# YiWallet-Enc-memory.net
KiCad netlist of a schematic drawn in Altium Designer
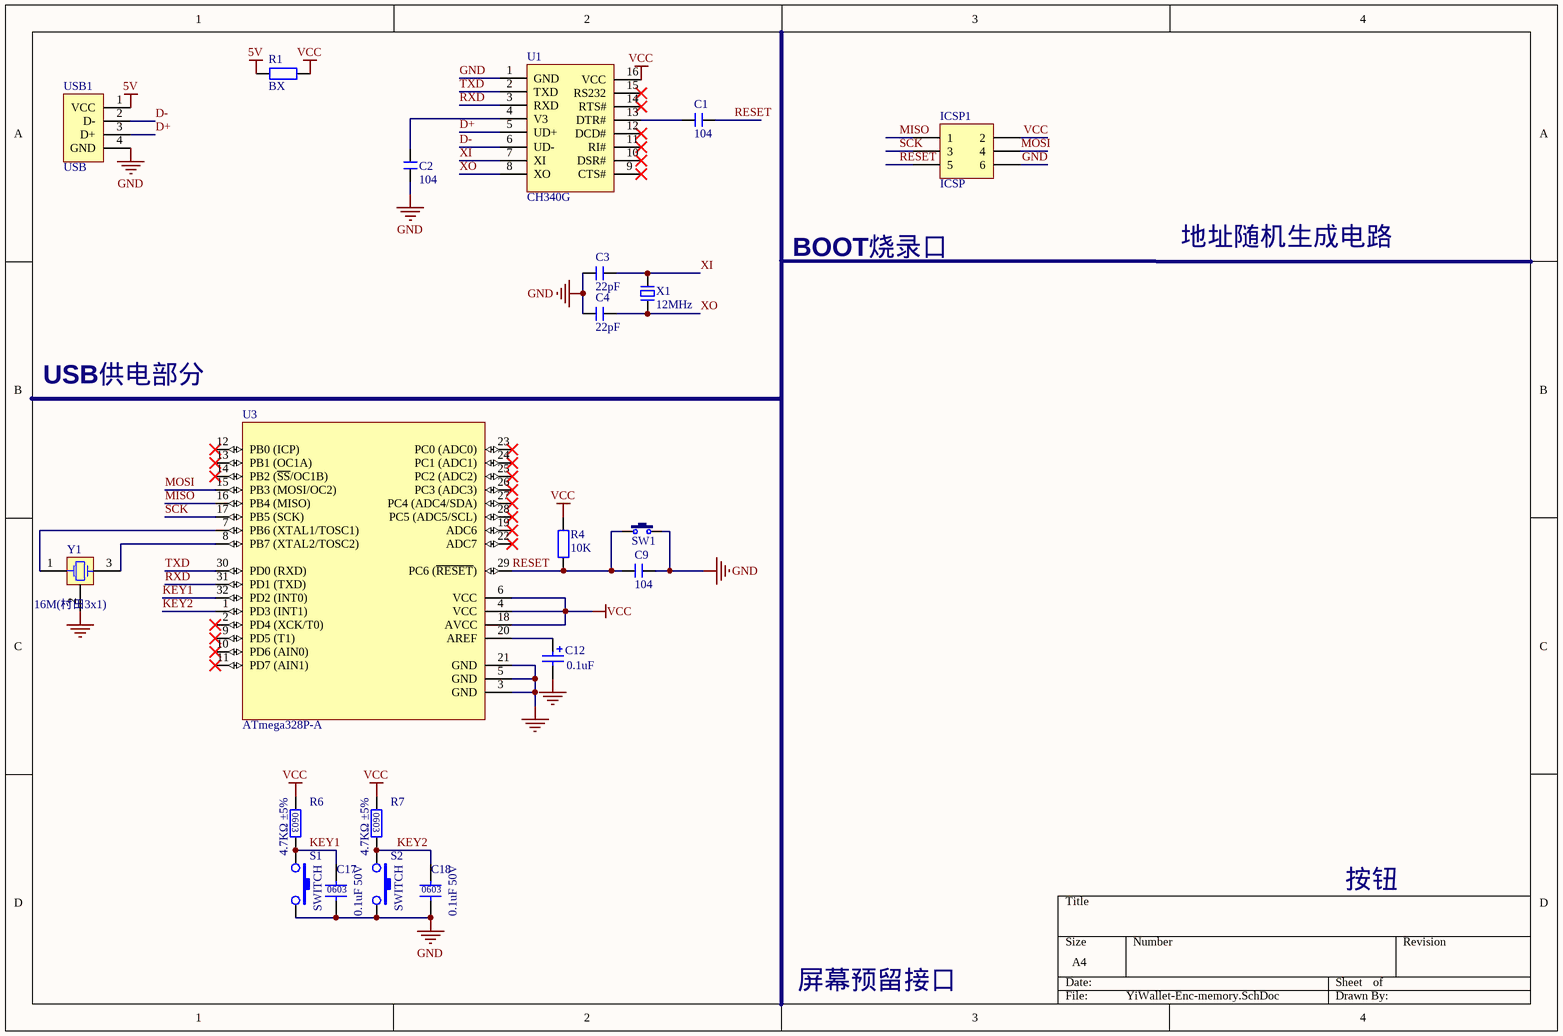
[diagram p0: YiWallet-Enc-memory.SchDoc]

(export (version "E")
  (design (tool "Eeschema 10.0.6"))
  (components
    (comp (ref "C1")
      (value "104")
      (footprint "C 0603_L")
      (description "无极性贴片电容")
      (fields (field (name "版权归属") "源创客"))
      (libsource (lib "3.1   - 电阻-电容-电感") (part "C"))
    )
    (comp (ref "C2")
      (value "104")
      (footprint "C 0603_L")
      (description "无极性贴片电容")
      (fields (field (name "版权归属") "源创客"))
      (libsource (lib "3.1   - 电阻-电容-电感") (part "C"))
    )
    (comp (ref "C3")
      (value "22pF")
      (footprint "C 0603_L")
      (description "无极性贴片电容")
      (fields (field (name "版权归属") "源创客"))
      (libsource (lib "3.1   - 电阻-电容-电感") (part "C"))
    )
    (comp (ref "C4")
      (value "22pF")
      (footprint "C 0603_L")
      (description "无极性贴片电容")
      (fields (field (name "版权归属") "源创客"))
      (libsource (lib "3.1   - 电阻-电容-电感") (part "C"))
    )
    (comp (ref "C9")
      (value "104")
      (footprint "C 0603_L")
      (description "无极性贴片电容")
      (fields (field (name "版权归属") "源创客"))
      (libsource (lib "3.1   - 电阻-电容-电感") (part "C"))
    )
    (comp (ref "C12")
      (value "0.1uF")
      (footprint "C 0603_L")
      (description "Polarized Capacitor (Surface Mount)")
      (fields (field (name "PUBLISHER") "Altium Limited"))
      (libsource (lib "Miscellaneous Devices") (part "Cap Pol3"))
    )
    (comp (ref "C17")
      (value "0.1uF 50V")
      (footprint "C 0603_L")
      (description "贴片电容 0.1uF 50V ±10% -55~+125℃ 0603 X7R CL10B104KB8NNNC")
      (libsource (lib "CLOU-BZ-BetaV0") (part "C-0.1uF 50V 0603"))
    )
    (comp (ref "C18")
      (value "0.1uF 50V")
      (footprint "C 0603_L")
      (description "贴片电容 0.1uF 50V ±10% -55~+125℃ 0603 X7R CL10B104KB8NNNC")
      (libsource (lib "CLOU-BZ-BetaV0") (part "C-0.1uF 50V 0603"))
    )
    (comp (ref "ICSP1")
      (value "ICSP")
      (footprint "HDR2X3")
      (description "Header, 3-Pin, Dual row")
      (fields (field (name "PUBLISHER") "Altium Limited"))
      (libsource (lib "Miscellaneous Connectors") (part "Header 3X2"))
    )
    (comp (ref "R1")
      (value "BX")
      (footprint "R 0603_L")
      (description "贴片电阻")
      (fields (field (name "版权归属") "源创客"))
      (libsource (lib "3.1   - 电阻-电容-电感") (part "R"))
    )
    (comp (ref "R4")
      (value "10K")
      (footprint "R 0603_L")
      (description "贴片电阻")
      (fields (field (name "版权归属") "源创客"))
      (libsource (lib "3.1   - 电阻-电容-电感") (part "R"))
    )
    (comp (ref "R6")
      (value "4.7KΩ ±5%")
      (footprint "C 0603_L")
      (description "贴片电阻 4.7KΩ 1/10W ±5% ±200ppm 0603")
      (libsource (lib "CLOU-BZ-BetaV0") (part "R-4K7 0603 5%"))
    )
    (comp (ref "R7")
      (value "4.7KΩ ±5%")
      (footprint "C 0603_L")
      (description "贴片电阻 4.7KΩ 1/10W ±5% ±200ppm 0603")
      (libsource (lib "CLOU-BZ-BetaV0") (part "R-4K7 0603 5%"))
    )
    (comp (ref "S1")
      (value "SWITCH")
      (footprint "TSW 3*6*4.3-S-W")
      (description "开关（轻触）")
      (libsource (lib "NEW library") (part "SW_PB6.2*6.2_5"))
    )
    (comp (ref "S2")
      (value "SWITCH")
      (footprint "TSW 3*6*4.3-S-W")
      (description "开关（轻触）")
      (libsource (lib "NEW library") (part "SW_PB6.2*6.2_5"))
    )
    (comp (ref "SW1")
      (value "3x6x5")
      (footprint "TSW 3*6*4.3-S-W")
      (description "3x6轻触开关")
      (fields (field (name "版权归属") "源创客"))
      (libsource (lib "5.1   - 按键-开关") (part "TSW 3x6"))
    )
    (comp (ref "U1") (value "CH340G") (footprint "SO-16") (libsource (lib "PCB_Project") (part "CH340G")))
    (comp (ref "U3")
      (value "ATmega328P-A")
      (footprint "TQFP32-7*7")
      (description "8-Bit AVR Microcontroller with 8K Bytes of In-System Programmable Flash Memory")
      (libsource (lib "Atmel Microcontroller 8-Bit AVR") (part "ATmega8-16AC"))
    )
    (comp (ref "USB1")
      (value "USB")
      (footprint "USB_A/P_A")
      (description "USB-A型公接口")
      (fields (field (name "版权归属") "源创客"))
      (libsource (lib "4.1   - 接口类") (part "USB-A/P"))
    )
    (comp (ref "X1")
      (value "12MHz")
      (footprint "OSC HC-49S")
      (description "2脚无源脚晶振")
      (fields (field (name "版权归属") "源创客"))
      (libsource (lib "10.1 - 保险丝-晶振") (part "XTAL-2P"))
    )
    (comp (ref "Y1")
      (value "16M(村田3x1)")
      (footprint "X-CPX20")
      (description "Crystal Oscillator, 3rd In-Line Lead Version")
      (fields (field (name "PUBLISHER") "Altium Limited"))
      (libsource (lib "ECS Crystal Oscillator") (part "ECS-35-17-4-3IL"))
    )
  )
  (nets
    (net (code "1") (name "/D+") (class "Default")
      (node (ref "U1") (pin "5") (pinfunction "UD+_5") (pintype "passive"))
      (node (ref "USB1") (pin "3") (pinfunction "D+_3") (pintype "passive"))
    )
    (net (code "2") (name "/D-") (class "Default")
      (node (ref "U1") (pin "6") (pinfunction "UD-_6") (pintype "passive"))
      (node (ref "USB1") (pin "2") (pinfunction "D-_2") (pintype "passive"))
    )
    (net (code "3") (name "/KEY1") (class "Default")
      (node (ref "C17") (pin "1") (pinfunction "1_1") (pintype "passive"))
      (node (ref "R6") (pin "2") (pinfunction "2_2") (pintype "passive"))
      (node (ref "S1") (pin "2") (pinfunction "2_2") (pintype "passive"))
      (node (ref "U3") (pin "32") (pinfunction "PD2_(INT0)_32") (pintype "bidirectional"))
    )
    (net (code "4") (name "/KEY2") (class "Default")
      (node (ref "C18") (pin "1") (pinfunction "1_1") (pintype "passive"))
      (node (ref "R7") (pin "2") (pinfunction "2_2") (pintype "passive"))
      (node (ref "S2") (pin "2") (pinfunction "2_2") (pintype "passive"))
      (node (ref "U3") (pin "1") (pinfunction "PD3_(INT1)_1") (pintype "bidirectional"))
    )
    (net (code "5") (name "/MISO") (class "Default")
      (node (ref "ICSP1") (pin "1") (pinfunction "1_1") (pintype "passive"))
      (node (ref "U3") (pin "16") (pinfunction "PB4_(MISO)_16") (pintype "bidirectional"))
    )
    (net (code "6") (name "/MOSI") (class "Default")
      (node (ref "ICSP1") (pin "4") (pinfunction "4_4") (pintype "passive"))
      (node (ref "U3") (pin "15") (pinfunction "PB3_(MOSI/OC2)_15") (pintype "bidirectional"))
    )
    (net (code "7") (name "/RESET") (class "Default")
      (node (ref "C1") (pin "2") (pinfunction "2_2") (pintype "passive"))
      (node (ref "C9") (pin "1") (pinfunction "1_1") (pintype "passive"))
      (node (ref "ICSP1") (pin "5") (pinfunction "5_5") (pintype "passive"))
      (node (ref "R4") (pin "1") (pinfunction "1_1") (pintype "passive"))
      (node (ref "SW1") (pin "1") (pinfunction "1_1") (pintype "passive"))
      (node (ref "U3") (pin "29") (pinfunction "PC6_(~{RESET})_29") (pintype "bidirectional"))
    )
    (net (code "8") (name "/RXD") (class "Default")
      (node (ref "U1") (pin "3") (pinfunction "RXD_3") (pintype "passive"))
      (node (ref "U3") (pin "31") (pinfunction "PD1_(TXD)_31") (pintype "bidirectional"))
    )
    (net (code "9") (name "/SCK") (class "Default")
      (node (ref "ICSP1") (pin "3") (pinfunction "3_3") (pintype "passive"))
      (node (ref "U3") (pin "17") (pinfunction "PB5_(SCK)_17") (pintype "bidirectional"))
    )
    (net (code "10") (name "/TXD") (class "Default")
      (node (ref "U1") (pin "2") (pinfunction "TXD_2") (pintype "passive"))
      (node (ref "U3") (pin "30") (pinfunction "PD0_(RXD)_30") (pintype "bidirectional"))
    )
    (net (code "11") (name "/XI") (class "Default")
      (node (ref "C3") (pin "2") (pinfunction "2_2") (pintype "passive"))
      (node (ref "U1") (pin "7") (pinfunction "XI_7") (pintype "passive"))
      (node (ref "X1") (pin "2") (pinfunction "2_2") (pintype "passive"))
    )
    (net (code "12") (name "/XO") (class "Default")
      (node (ref "C4") (pin "2") (pinfunction "2_2") (pintype "passive"))
      (node (ref "U1") (pin "8") (pinfunction "XO_8") (pintype "passive"))
      (node (ref "X1") (pin "1") (pinfunction "1_1") (pintype "passive"))
    )
    (net (code "13") (name "5V") (class "Default")
      (node (ref "R1") (pin "1") (pinfunction "1_1") (pintype "passive"))
      (node (ref "USB1") (pin "1") (pinfunction "VCC_1") (pintype "passive"))
    )
    (net (code "14") (name "GND") (class "Default")
      (node (ref "C12") (pin "2") (pinfunction "2_2") (pintype "passive"))
      (node (ref "C17") (pin "2") (pinfunction "2_2") (pintype "passive"))
      (node (ref "C18") (pin "2") (pinfunction "2_2") (pintype "passive"))
      (node (ref "C2") (pin "1") (pinfunction "1_1") (pintype "passive"))
      (node (ref "C3") (pin "1") (pinfunction "1_1") (pintype "passive"))
      (node (ref "C4") (pin "1") (pinfunction "1_1") (pintype "passive"))
      (node (ref "C9") (pin "2") (pinfunction "2_2") (pintype "passive"))
      (node (ref "ICSP1") (pin "6") (pinfunction "6_6") (pintype "passive"))
      (node (ref "S1") (pin "1") (pinfunction "1_1") (pintype "passive"))
      (node (ref "S2") (pin "1") (pinfunction "1_1") (pintype "passive"))
      (node (ref "SW1") (pin "2") (pinfunction "2_2") (pintype "passive"))
      (node (ref "U1") (pin "1") (pinfunction "GND_1") (pintype "passive"))
      (node (ref "U3") (pin "21") (pinfunction "GND_21") (pintype "power_in"))
      (node (ref "U3") (pin "3") (pinfunction "GND_3") (pintype "power_in"))
      (node (ref "U3") (pin "5") (pinfunction "GND_5") (pintype "power_in"))
      (node (ref "USB1") (pin "4") (pinfunction "GND_4") (pintype "passive"))
      (node (ref "Y1") (pin "2") (pinfunction "COM_2") (pintype "passive"))
    )
    (net (code "15") (name "Net-(U1-DTR#)") (class "Default")
      (node (ref "C1") (pin "1") (pinfunction "1_1") (pintype "passive"))
      (node (ref "U1") (pin "13") (pinfunction "DTR#_13") (pintype "passive"))
    )
    (net (code "16") (name "Net-(U1-V3)") (class "Default")
      (node (ref "C2") (pin "2") (pinfunction "2_2") (pintype "passive"))
      (node (ref "U1") (pin "4") (pinfunction "V3_4") (pintype "passive"))
    )
    (net (code "17") (name "Net-(U3-AREF)") (class "Default")
      (node (ref "C12") (pin "1") (pinfunction "1_1") (pintype "passive"))
      (node (ref "U3") (pin "20") (pinfunction "AREF_20") (pintype "passive"))
    )
    (net (code "18") (name "Net-(U3-PB6_(XTAL1{slash}TOSC1))") (class "Default")
      (node (ref "U3") (pin "7") (pinfunction "PB6_(XTAL1/TOSC1)_7") (pintype "bidirectional"))
      (node (ref "Y1") (pin "1") (pinfunction "OSC1_1") (pintype "passive"))
    )
    (net (code "19") (name "Net-(U3-PB7_(XTAL2{slash}TOSC2))") (class "Default")
      (node (ref "U3") (pin "8") (pinfunction "PB7_(XTAL2/TOSC2)_8") (pintype "bidirectional"))
      (node (ref "Y1") (pin "3") (pinfunction "OSC2_3") (pintype "passive"))
    )
    (net (code "20") (name "VCC") (class "Default")
      (node (ref "ICSP1") (pin "2") (pinfunction "2_2") (pintype "passive"))
      (node (ref "R1") (pin "2") (pinfunction "2_2") (pintype "passive"))
      (node (ref "R4") (pin "2") (pinfunction "2_2") (pintype "passive"))
      (node (ref "R6") (pin "1") (pinfunction "1_1") (pintype "passive"))
      (node (ref "R7") (pin "1") (pinfunction "1_1") (pintype "passive"))
      (node (ref "U1") (pin "16") (pinfunction "VCC_16") (pintype "passive"))
      (node (ref "U3") (pin "18") (pinfunction "AVCC_18") (pintype "power_in"))
      (node (ref "U3") (pin "4") (pinfunction "VCC_4") (pintype "power_in"))
      (node (ref "U3") (pin "6") (pinfunction "VCC_6") (pintype "power_in"))
    )
    (net (code "21") (name "unconnected-(U1-CTS#-Pad9)") (class "Default")
      (node (ref "U1") (pin "9") (pinfunction "CTS#_9") (pintype "passive+no_connect"))
    )
    (net (code "22") (name "unconnected-(U1-DCD#-Pad12)") (class "Default")
      (node (ref "U1") (pin "12") (pinfunction "DCD#_12") (pintype "passive+no_connect"))
    )
    (net (code "23") (name "unconnected-(U1-DSR#-Pad10)") (class "Default")
      (node (ref "U1") (pin "10") (pinfunction "DSR#_10") (pintype "passive+no_connect"))
    )
    (net (code "24") (name "unconnected-(U1-RI#-Pad11)") (class "Default")
      (node (ref "U1") (pin "11") (pinfunction "RI#_11") (pintype "passive+no_connect"))
    )
    (net (code "25") (name "unconnected-(U1-RS232-Pad15)") (class "Default")
      (node (ref "U1") (pin "15") (pinfunction "RS232_15") (pintype "passive+no_connect"))
    )
    (net (code "26") (name "unconnected-(U1-RTS#-Pad14)") (class "Default")
      (node (ref "U1") (pin "14") (pinfunction "RTS#_14") (pintype "passive+no_connect"))
    )
    (net (code "27") (name "unconnected-(U3-ADC6-Pad19)") (class "Default")
      (node (ref "U3") (pin "19") (pinfunction "ADC6_19") (pintype "bidirectional+no_connect"))
    )
    (net (code "28") (name "unconnected-(U3-ADC7-Pad22)") (class "Default")
      (node (ref "U3") (pin "22") (pinfunction "ADC7_22") (pintype "bidirectional+no_connect"))
    )
    (net (code "29") (name "unconnected-(U3-PB0_(ICP)-Pad12)") (class "Default")
      (node (ref "U3") (pin "12") (pinfunction "PB0_(ICP)_12") (pintype "bidirectional+no_connect"))
    )
    (net (code "30") (name "unconnected-(U3-PB1_(OC1A)-Pad13)") (class "Default")
      (node (ref "U3") (pin "13") (pinfunction "PB1_(OC1A)_13") (pintype "bidirectional+no_connect"))
    )
    (net (code "31") (name "unconnected-(U3-PB2_(~{SS}{slash}OC1B)-Pad14)") (class "Default")
      (node (ref "U3") (pin "14") (pinfunction "PB2_(~{SS}/OC1B)_14") (pintype "bidirectional+no_connect"))
    )
    (net (code "32") (name "unconnected-(U3-PC0_(ADC0)-Pad23)") (class "Default")
      (node (ref "U3") (pin "23") (pinfunction "PC0_(ADC0)_23") (pintype "bidirectional+no_connect"))
    )
    (net (code "33") (name "unconnected-(U3-PC1_(ADC1)-Pad24)") (class "Default")
      (node (ref "U3") (pin "24") (pinfunction "PC1_(ADC1)_24") (pintype "bidirectional+no_connect"))
    )
    (net (code "34") (name "unconnected-(U3-PC2_(ADC2)-Pad25)") (class "Default")
      (node (ref "U3") (pin "25") (pinfunction "PC2_(ADC2)_25") (pintype "bidirectional+no_connect"))
    )
    (net (code "35") (name "unconnected-(U3-PC3_(ADC3)-Pad26)") (class "Default")
      (node (ref "U3") (pin "26") (pinfunction "PC3_(ADC3)_26") (pintype "bidirectional+no_connect"))
    )
    (net (code "36") (name "unconnected-(U3-PC4_(ADC4{slash}SDA)-Pad27)") (class "Default")
      (node (ref "U3") (pin "27") (pinfunction "PC4_(ADC4/SDA)_27") (pintype "bidirectional+no_connect"))
    )
    (net (code "37") (name "unconnected-(U3-PC5_(ADC5{slash}SCL)-Pad28)") (class "Default")
      (node (ref "U3") (pin "28") (pinfunction "PC5_(ADC5/SCL)_28") (pintype "bidirectional+no_connect"))
    )
    (net (code "38") (name "unconnected-(U3-PD4_(XCK{slash}T0)-Pad2)") (class "Default")
      (node (ref "U3") (pin "2") (pinfunction "PD4_(XCK/T0)_2") (pintype "bidirectional+no_connect"))
    )
    (net (code "39") (name "unconnected-(U3-PD5_(T1)-Pad9)") (class "Default")
      (node (ref "U3") (pin "9") (pinfunction "PD5_(T1)_9") (pintype "bidirectional+no_connect"))
    )
    (net (code "40") (name "unconnected-(U3-PD6_(AIN0)-Pad10)") (class "Default")
      (node (ref "U3") (pin "10") (pinfunction "PD6_(AIN0)_10") (pintype "bidirectional+no_connect"))
    )
    (net (code "41") (name "unconnected-(U3-PD7_(AIN1)-Pad11)") (class "Default")
      (node (ref "U3") (pin "11") (pinfunction "PD7_(AIN1)_11") (pintype "bidirectional+no_connect"))
    )
  )
)
